# SaLAltimeter.net
KiCad netlist of a schematic drawn in EAGLE
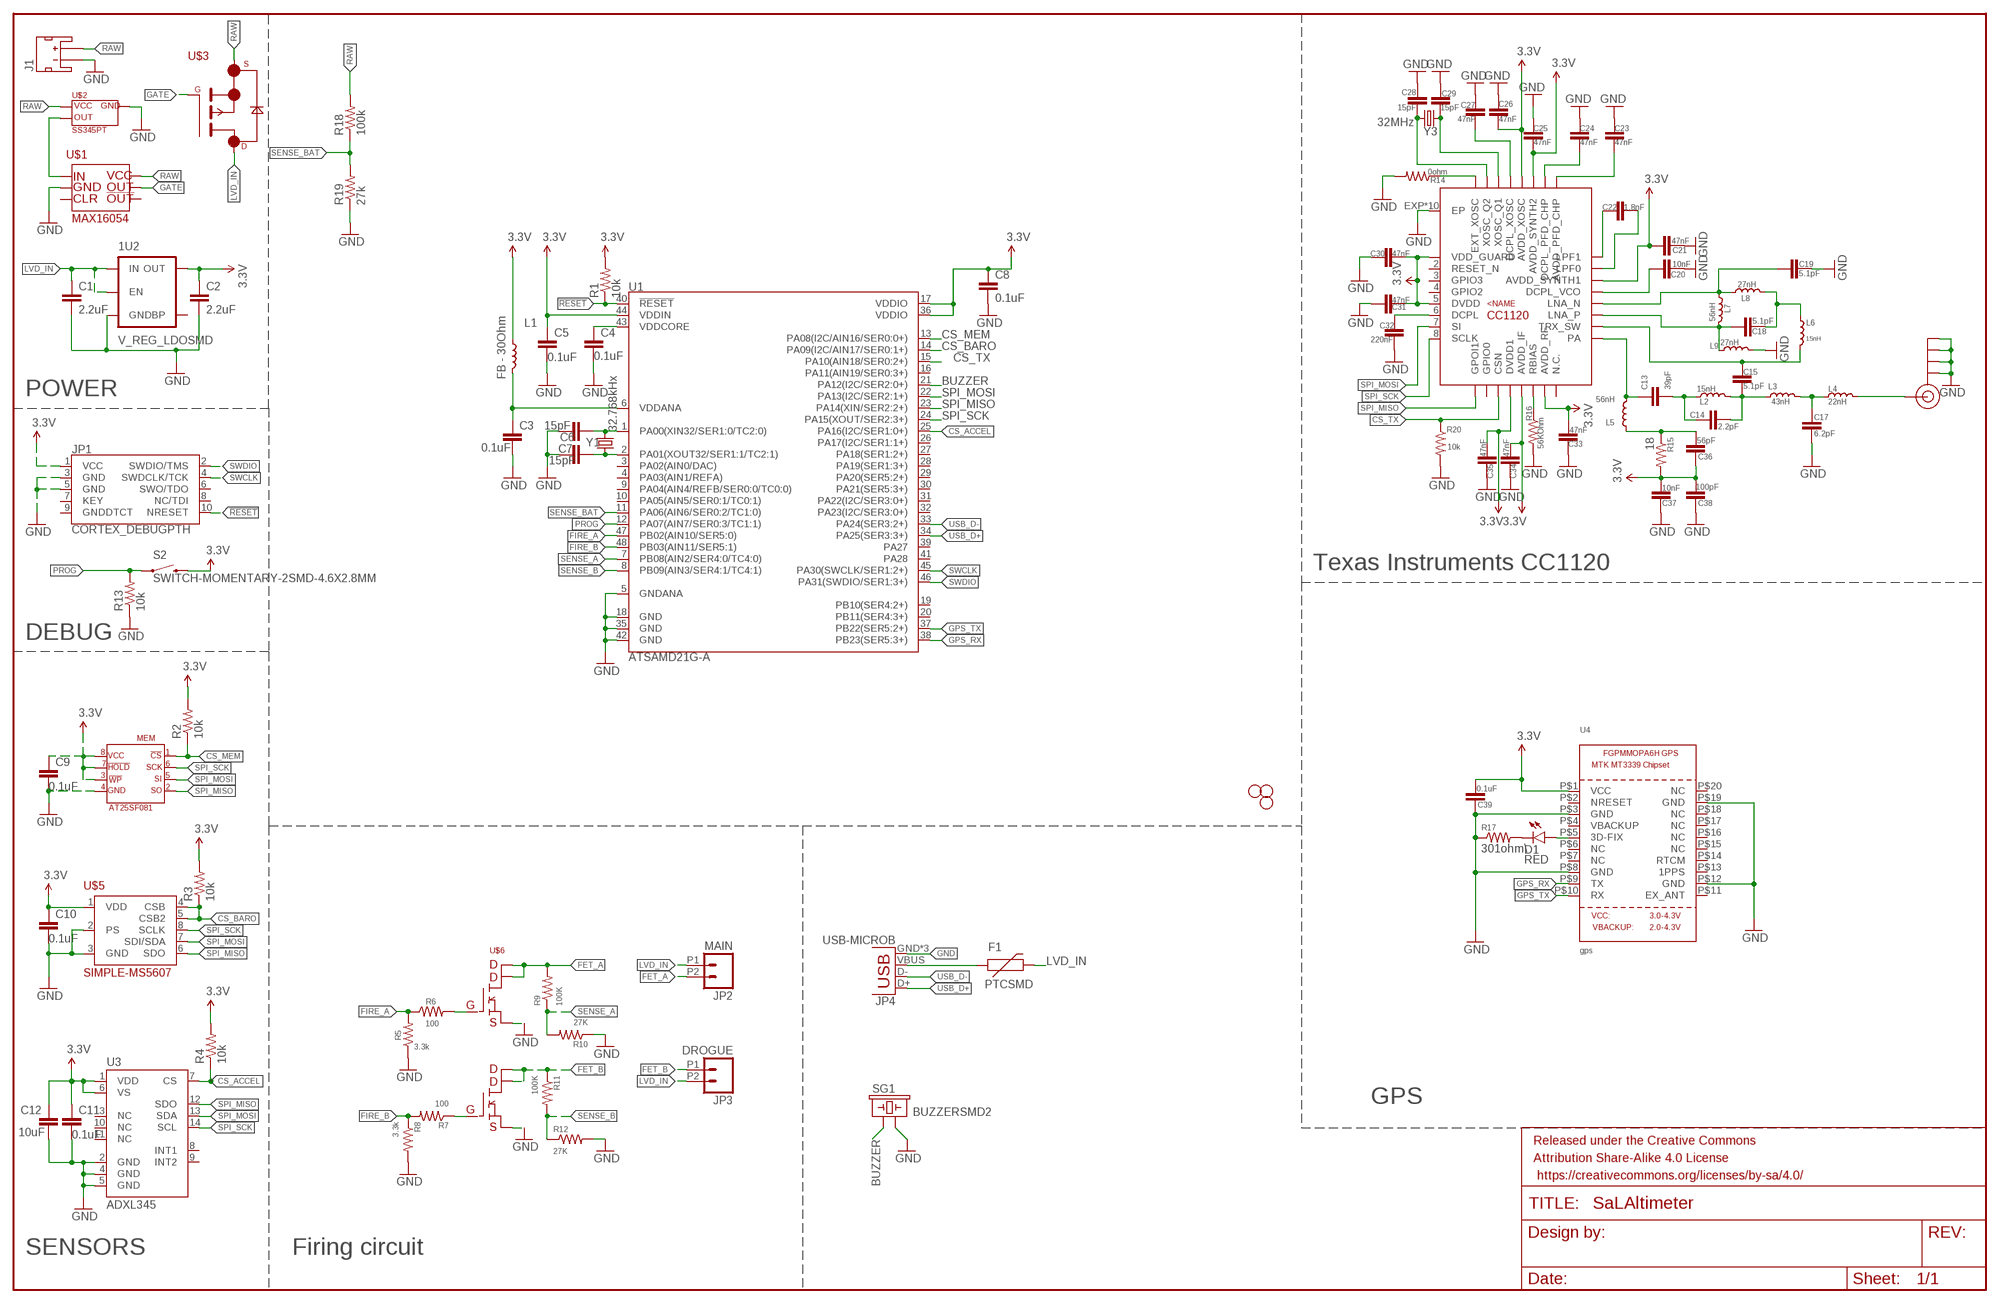
[diagram p0: schematic, sheet 1]

(export (version "E")
  (design (tool "Eeschema 10.0.6"))
  (components
    (comp (ref "1U2")
      (value "V_REG_LDOSMD")
      (footprint "eagle-import:SOT23-5")
      (libsource (lib "eagle-import") (part "V_REG_LDOSMD"))
    )
    (comp (ref "C1")
      (value "2.2uF")
      (footprint "eagle-import:0603-CAP")
      (libsource (lib "eagle-import") (part "CAP0603-CAP"))
    )
    (comp (ref "C2")
      (value "2.2uF")
      (footprint "eagle-import:0603-CAP")
      (libsource (lib "eagle-import") (part "CAP0603-CAP"))
    )
    (comp (ref "C3")
      (value "0.1uF")
      (footprint "eagle-import:0402-CAP")
      (libsource (lib "eagle-import") (part "SparkFun-Passives_CAP0402-CAP"))
    )
    (comp (ref "C4")
      (value "0.1uF")
      (footprint "eagle-import:0402-CAP")
      (libsource (lib "eagle-import") (part "SparkFun-Passives_CAP0402-CAP"))
    )
    (comp (ref "C5")
      (value "0.1uF")
      (footprint "eagle-import:0402-CAP")
      (libsource (lib "eagle-import") (part "SparkFun-Passives_CAP0402-CAP"))
    )
    (comp (ref "C6")
      (value "15pF")
      (footprint "eagle-import:0402-CAP")
      (libsource (lib "eagle-import") (part "SparkFun-Passives_CAP0402-CAP"))
    )
    (comp (ref "C7")
      (value "15pF")
      (footprint "eagle-import:0402-CAP")
      (libsource (lib "eagle-import") (part "SparkFun-Passives_CAP0402-CAP"))
    )
    (comp (ref "C8")
      (value "0.1uF")
      (footprint "eagle-import:0402-CAP")
      (libsource (lib "eagle-import") (part "SparkFun-Passives_CAP0402-CAP"))
    )
    (comp (ref "C9")
      (value "0.1uF")
      (footprint "eagle-import:0402-CAP")
      (libsource (lib "eagle-import") (part "SparkFun-Passives_CAP0402-CAP"))
    )
    (comp (ref "C10")
      (value "0.1uF")
      (footprint "eagle-import:0402-CAP")
      (libsource (lib "eagle-import") (part "SparkFun-Passives_CAP0402-CAP"))
    )
    (comp (ref "C11")
      (value "0.1uF")
      (footprint "eagle-import:0402-CAP")
      (libsource (lib "eagle-import") (part "SparkFun-Passives_CAP0402-CAP"))
    )
    (comp (ref "C12")
      (value "10uF")
      (footprint "eagle-import:0402-CAP")
      (libsource (lib "eagle-import") (part "SparkFun-Passives_CAP0402-CAP"))
    )
    (comp (ref "C13")
      (value "39pF")
      (footprint "eagle-import:0402-CAP")
      (libsource (lib "eagle-import") (part "CAP0402-CAP"))
    )
    (comp (ref "C14")
      (value "2.2pF")
      (footprint "eagle-import:0402-CAP")
      (libsource (lib "eagle-import") (part "CAP0402-CAP"))
    )
    (comp (ref "C15")
      (value "5.1pF")
      (footprint "eagle-import:0402-CAP")
      (libsource (lib "eagle-import") (part "CAP0402-CAP"))
    )
    (comp (ref "C17")
      (value "6.2pF")
      (footprint "eagle-import:0402-CAP")
      (libsource (lib "eagle-import") (part "CAP0402-CAP"))
    )
    (comp (ref "C18")
      (value "5.1pF")
      (footprint "eagle-import:0402-CAP")
      (libsource (lib "eagle-import") (part "CAP0402-CAP"))
    )
    (comp (ref "C19")
      (value "5.1pF")
      (footprint "eagle-import:0402-CAP")
      (libsource (lib "eagle-import") (part "CAP0402-CAP"))
    )
    (comp (ref "C20")
      (value "10nF")
      (footprint "eagle-import:0402-CAP")
      (libsource (lib "eagle-import") (part "CAP0402-CAP"))
    )
    (comp (ref "C21")
      (value "47nF")
      (footprint "eagle-import:0402-CAP")
      (libsource (lib "eagle-import") (part "CAP0402-CAP"))
    )
    (comp (ref "C22")
      (value "1.8nF")
      (footprint "eagle-import:0402-CAP")
      (libsource (lib "eagle-import") (part "CAP0402-CAP"))
    )
    (comp (ref "C23")
      (value "47nF")
      (footprint "eagle-import:0402-CAP")
      (libsource (lib "eagle-import") (part "CAP0402-CAP"))
    )
    (comp (ref "C24")
      (value "47nF")
      (footprint "eagle-import:0402-CAP")
      (libsource (lib "eagle-import") (part "CAP0402-CAP"))
    )
    (comp (ref "C25")
      (value "47nF")
      (footprint "eagle-import:0402-CAP")
      (libsource (lib "eagle-import") (part "CAP0402-CAP"))
    )
    (comp (ref "C26")
      (value "47nF")
      (footprint "eagle-import:0402-CAP")
      (libsource (lib "eagle-import") (part "CAP0402-CAP"))
    )
    (comp (ref "C27")
      (value "47nF")
      (footprint "eagle-import:0402-CAP")
      (libsource (lib "eagle-import") (part "CAP0402-CAP"))
    )
    (comp (ref "C28")
      (value "15pF")
      (footprint "eagle-import:0402-CAP")
      (libsource (lib "eagle-import") (part "CAP0402-CAP"))
    )
    (comp (ref "C29")
      (value "15pF")
      (footprint "eagle-import:0402-CAP")
      (libsource (lib "eagle-import") (part "CAP0402-CAP"))
    )
    (comp (ref "C30")
      (value "47nF")
      (footprint "eagle-import:0402-CAP")
      (libsource (lib "eagle-import") (part "CAP0402-CAP"))
    )
    (comp (ref "C31")
      (value "47nF")
      (footprint "eagle-import:0402-CAP")
      (libsource (lib "eagle-import") (part "CAP0402-CAP"))
    )
    (comp (ref "C32")
      (value "220nF")
      (footprint "eagle-import:0402-CAP")
      (libsource (lib "eagle-import") (part "CAP0402-CAP"))
    )
    (comp (ref "C33")
      (value "47nF")
      (footprint "eagle-import:0402-CAP")
      (libsource (lib "eagle-import") (part "CAP0402-CAP"))
    )
    (comp (ref "C34")
      (value "47nF")
      (footprint "eagle-import:0402-CAP")
      (libsource (lib "eagle-import") (part "CAP0402-CAP"))
    )
    (comp (ref "C35")
      (value "47nF")
      (footprint "eagle-import:0402-CAP")
      (libsource (lib "eagle-import") (part "CAP0402-CAP"))
    )
    (comp (ref "C36")
      (value "56pF")
      (footprint "eagle-import:0402-CAP")
      (libsource (lib "eagle-import") (part "CAP0402-CAP"))
    )
    (comp (ref "C37")
      (value "10nF")
      (footprint "eagle-import:0402-CAP")
      (libsource (lib "eagle-import") (part "CAP0402-CAP"))
    )
    (comp (ref "C38")
      (value "100pF")
      (footprint "eagle-import:0402-CAP")
      (libsource (lib "eagle-import") (part "CAP0402-CAP"))
    )
    (comp (ref "C39")
      (value "0.1uF")
      (footprint "eagle-import:0402-CAP")
      (libsource (lib "eagle-import") (part "CAP0402-CAP"))
    )
    (comp (ref "D1")
      (value "RED")
      (footprint "eagle-import:LED-0603")
      (libsource (lib "eagle-import") (part "LED-RED0603"))
    )
    (comp (ref "F1")
      (value "PTCSMD")
      (footprint "eagle-import:PTC-1206")
      (libsource (lib "eagle-import") (part "PTCSMD"))
    )
    (comp (ref "FRAME1")
      (value "FRAME-LEDGER")
      (footprint "eagle-import:CREATIVE_COMMONS")
      (libsource (lib "eagle-import") (part "FRAME-LEDGER"))
    )
    (comp (ref "J$1")
      (value "SMA_EDGE")
      (footprint "eagle-import:SMA-EDGE")
      (libsource (lib "eagle-import") (part "SMA_EDGE"))
    )
    (comp (ref "J1")
      (value "BAT")
      (footprint "eagle-import:JST-2-SMD")
      (libsource (lib "eagle-import") (part "JST_2MM_MALE"))
    )
    (comp (ref "JP1")
      (value "CORTEX_DEBUGPTH")
      (footprint "eagle-import:2X5-PTH-1.27MM")
      (libsource (lib "eagle-import") (part "CORTEX_DEBUGPTH"))
    )
    (comp (ref "JP2")
      (value "MAIN")
      (footprint "eagle-import:1X02_2.54_SCREWTERM")
      (libsource (lib "eagle-import") (part "M022.54MM_SCREWTERM"))
    )
    (comp (ref "JP3")
      (value "DROGUE")
      (footprint "eagle-import:1X02_2.54_SCREWTERM")
      (libsource (lib "eagle-import") (part "M022.54MM_SCREWTERM"))
    )
    (comp (ref "JP4")
      (value "USB-MICROB")
      (footprint "eagle-import:USB-MICROB")
      (libsource (lib "eagle-import") (part "USB-MICROB"))
    )
    (comp (ref "L1")
      (value "FB - 30Ohm")
      (footprint "eagle-import:0603")
      (libsource (lib "eagle-import") (part "INDUCTOR0603"))
    )
    (comp (ref "L2")
      (value "15nH")
      (footprint "eagle-import:C0402")
      (libsource (lib "eagle-import") (part "INDUCTOR0402"))
    )
    (comp (ref "L3")
      (value "43nH")
      (footprint "eagle-import:C0402")
      (libsource (lib "eagle-import") (part "INDUCTOR0402"))
    )
    (comp (ref "L4")
      (value "22nH")
      (footprint "eagle-import:C0402")
      (libsource (lib "eagle-import") (part "INDUCTOR0402"))
    )
    (comp (ref "L5")
      (value "56nH")
      (footprint "eagle-import:C0402")
      (libsource (lib "eagle-import") (part "INDUCTOR0402"))
    )
    (comp (ref "L6")
      (value "15nH")
      (footprint "eagle-import:C0402")
      (libsource (lib "eagle-import") (part "INDUCTOR0402"))
    )
    (comp (ref "L7")
      (value "56nH")
      (footprint "eagle-import:C0402")
      (libsource (lib "eagle-import") (part "INDUCTOR0402"))
    )
    (comp (ref "L8")
      (value "27nH")
      (footprint "eagle-import:C0402")
      (libsource (lib "eagle-import") (part "INDUCTOR0402"))
    )
    (comp (ref "L9")
      (value "27nH")
      (footprint "eagle-import:C0402")
      (libsource (lib "eagle-import") (part "INDUCTOR0402"))
    )
    (comp (ref "MEM")
      (value "AT25SF081")
      (footprint "eagle-import:AT25SF081")
      (libsource (lib "eagle-import") (part "AT25SF081"))
    )
    (comp (ref "R1")
      (value "10k")
      (footprint "eagle-import:0402-RES")
      (libsource (lib "eagle-import") (part "RESISTOR0402-RES"))
    )
    (comp (ref "R2")
      (value "10k")
      (footprint "eagle-import:0402-RES")
      (libsource (lib "eagle-import") (part "RESISTOR0402-RES"))
    )
    (comp (ref "R3")
      (value "10k")
      (footprint "eagle-import:0402-RES")
      (libsource (lib "eagle-import") (part "RESISTOR0402-RES"))
    )
    (comp (ref "R4")
      (value "10k")
      (footprint "eagle-import:0402-RES")
      (libsource (lib "eagle-import") (part "RESISTOR0402-RES"))
    )
    (comp (ref "R5")
      (value "3.3k")
      (footprint "eagle-import:0402-RES")
      (libsource (lib "eagle-import") (part "RESISTOR0402"))
    )
    (comp (ref "R6")
      (value "100")
      (footprint "eagle-import:0402-RES")
      (libsource (lib "eagle-import") (part "RESISTOR0402"))
    )
    (comp (ref "R7")
      (value "100")
      (footprint "eagle-import:0402-RES")
      (libsource (lib "eagle-import") (part "RESISTOR0402"))
    )
    (comp (ref "R8")
      (value "3.3k")
      (footprint "eagle-import:0402-RES")
      (libsource (lib "eagle-import") (part "RESISTOR0402"))
    )
    (comp (ref "R9")
      (value "100K")
      (footprint "eagle-import:0402-RES")
      (libsource (lib "eagle-import") (part "RESISTOR0402"))
    )
    (comp (ref "R10")
      (value "27K")
      (footprint "eagle-import:0402-RES")
      (libsource (lib "eagle-import") (part "RESISTOR0402"))
    )
    (comp (ref "R11")
      (value "100K")
      (footprint "eagle-import:0402-RES")
      (libsource (lib "eagle-import") (part "RESISTOR0402"))
    )
    (comp (ref "R12")
      (value "27K")
      (footprint "eagle-import:0402-RES")
      (libsource (lib "eagle-import") (part "RESISTOR0402"))
    )
    (comp (ref "R13")
      (value "10k")
      (footprint "eagle-import:0402-RES")
      (libsource (lib "eagle-import") (part "RESISTOR0402-RES"))
    )
    (comp (ref "R14")
      (value "0ohm")
      (footprint "eagle-import:0402-RES")
      (libsource (lib "eagle-import") (part "RESISTOR0402-RES"))
    )
    (comp (ref "R15")
      (value "18")
      (footprint "eagle-import:0402-RES")
      (libsource (lib "eagle-import") (part "RESISTOR0402-RES"))
    )
    (comp (ref "R16")
      (value "56KOhm")
      (footprint "eagle-import:0402-RES")
      (libsource (lib "eagle-import") (part "RESISTOR0402-RES"))
    )
    (comp (ref "R17")
      (value "301ohm\\")
      (footprint "eagle-import:0402-RES")
      (libsource (lib "eagle-import") (part "RESISTOR0402-RES"))
    )
    (comp (ref "R18")
      (value "100k")
      (footprint "eagle-import:0402-RES")
      (libsource (lib "eagle-import") (part "RESISTOR0402-RES"))
    )
    (comp (ref "R19")
      (value "27k")
      (footprint "eagle-import:0402-RES")
      (libsource (lib "eagle-import") (part "RESISTOR0402-RES"))
    )
    (comp (ref "R20")
      (value "10k")
      (footprint "eagle-import:0402-RES")
      (libsource (lib "eagle-import") (part "RESISTOR0402-RES"))
    )
    (comp (ref "S2")
      (value "SWITCH-MOMENTARY-2SMD-4.6X2.8MM")
      (footprint "eagle-import:TACTILE_SWITCH_SMD_4.6X2.8MM")
      (libsource (lib "eagle-import") (part "SWITCH-MOMENTARY-2SMD-4.6X2.8MM"))
    )
    (comp (ref "SG1")
      (value "BUZZERSMD2")
      (footprint "eagle-import:BUZZER-CCV")
      (libsource (lib "eagle-import") (part "BUZZERSMD2"))
    )
    (comp (ref "STANDOFF1")
      (value "STAND-OFF")
      (footprint "eagle-import:STAND-OFF")
      (libsource (lib "eagle-import") (part "STAND-OFF"))
    )
    (comp (ref "STANDOFF2")
      (value "STAND-OFF")
      (footprint "eagle-import:STAND-OFF")
      (libsource (lib "eagle-import") (part "STAND-OFF"))
    )
    (comp (ref "STANDOFF3")
      (value "STAND-OFF")
      (footprint "eagle-import:STAND-OFF")
      (libsource (lib "eagle-import") (part "STAND-OFF"))
    )
    (comp (ref "U$1")
      (value "MAX16054")
      (footprint "eagle-import:MAX16054")
      (libsource (lib "eagle-import") (part "MAX16054"))
    )
    (comp (ref "U$2")
      (value "SS345PT")
      (footprint "eagle-import:SS345PT")
      (libsource (lib "eagle-import") (part "SS345PT"))
    )
    (comp (ref "U$3")
      (value "SI7615ADN")
      (footprint "eagle-import:SI7615ADN")
      (libsource (lib "eagle-import") (part "SI7615ADN"))
    )
    (comp (ref "U$5")
      (value "SIMPLE-MS5607")
      (footprint "eagle-import:MS5607")
      (libsource (lib "eagle-import") (part "SIMPLE-MS5607"))
    )
    (comp (ref "U$6")
      (value "SI7232DN")
      (footprint "eagle-import:SI7232DN")
      (libsource (lib "eagle-import") (part "SI7232DN"))
    )
    (comp (ref "U1")
      (value "ATSAMD21G-A")
      (footprint "eagle-import:TQFP-48")
      (libsource (lib "eagle-import") (part "ATSAMD21G-A"))
    )
    (comp (ref "U2")
      (value "CC1120")
      (footprint "eagle-import:CC1120")
      (libsource (lib "eagle-import") (part "CC1120"))
    )
    (comp (ref "U3")
      (value "ADXL345")
      (footprint "eagle-import:LGA14")
      (libsource (lib "eagle-import") (part "ADXL345"))
    )
    (comp (ref "U4")
      (value "gps")
      (footprint "eagle-import:FGPMMOPA6H")
      (libsource (lib "eagle-import") (part "GPS_FGPMMOPA6H"))
    )
    (comp (ref "Y1")
      (value "32.768kHx")
      (footprint "eagle-import:CRYSTAL-SMD-3.2X1.5MM")
      (libsource (lib "eagle-import") (part "CRYSTAL3.2X1.5MM"))
    )
    (comp (ref "Y3")
      (value "32MHz")
      (footprint "eagle-import:CRYSTAL-SMD-5X3")
      (libsource (lib "eagle-import") (part "CRYSTAL5X3"))
    )
  )
  (nets
    (net (code "1") (name "/BUZZER") (class "Default")
      (node (ref "SG1") (pin "+") (pinfunction "1_+") (pintype "passive"))
      (node (ref "U1") (pin "21") (pinfunction "PA12(I2C/SER2:0+)_21") (pintype "bidirectional"))
    )
    (net (code "2") (name "/~{RESET}") (class "Default")
      (node (ref "JP1") (pin "10") (pinfunction "NRESET_10") (pintype "bidirectional"))
      (node (ref "R1") (pin "1") (pinfunction "1_1") (pintype "passive"))
      (node (ref "U1") (pin "40") (pinfunction "~{RESET}_40") (pintype "bidirectional"))
    )
    (net (code "3") (name "3.3V") (class "Default")
      (node (ref "1U2") (pin "5") (pinfunction "OUT_5") (pintype "passive"))
      (node (ref "C10") (pin "1") (pinfunction "1_1") (pintype "passive"))
      (node (ref "C11") (pin "1") (pinfunction "1_1") (pintype "passive"))
      (node (ref "C12") (pin "1") (pinfunction "1_1") (pintype "passive"))
      (node (ref "C2") (pin "1") (pinfunction "1_1") (pintype "passive"))
      (node (ref "C21") (pin "1") (pinfunction "1_1") (pintype "passive"))
      (node (ref "C25") (pin "2") (pinfunction "2_2") (pintype "passive"))
      (node (ref "C26") (pin "2") (pinfunction "2_2") (pintype "passive"))
      (node (ref "C30") (pin "2") (pinfunction "2_2") (pintype "passive"))
      (node (ref "C31") (pin "2") (pinfunction "2_2") (pintype "passive"))
      (node (ref "C33") (pin "2") (pinfunction "2_2") (pintype "passive"))
      (node (ref "C34") (pin "2") (pinfunction "2_2") (pintype "passive"))
      (node (ref "C35") (pin "2") (pinfunction "2_2") (pintype "passive"))
      (node (ref "C36") (pin "1") (pinfunction "1_1") (pintype "passive"))
      (node (ref "C37") (pin "2") (pinfunction "2_2") (pintype "passive"))
      (node (ref "C38") (pin "2") (pinfunction "2_2") (pintype "passive"))
      (node (ref "C39") (pin "2") (pinfunction "2_2") (pintype "passive"))
      (node (ref "C5") (pin "1") (pinfunction "1_1") (pintype "passive"))
      (node (ref "C8") (pin "1") (pinfunction "1_1") (pintype "passive"))
      (node (ref "C9") (pin "1") (pinfunction "1_1") (pintype "passive"))
      (node (ref "JP1") (pin "1") (pinfunction "VCC_1") (pintype "bidirectional"))
      (node (ref "L1") (pin "1") (pinfunction "1_1") (pintype "passive"))
      (node (ref "MEM") (pin "!HOLD") (pinfunction "~{HOLD}_!HOLD") (pintype "bidirectional"))
      (node (ref "MEM") (pin "!WP") (pinfunction "~{WP}_!WP") (pintype "bidirectional"))
      (node (ref "MEM") (pin "VCC") (pinfunction "VCC_VCC") (pintype "bidirectional"))
      (node (ref "R1") (pin "2") (pinfunction "2_2") (pintype "passive"))
      (node (ref "R15") (pin "2") (pinfunction "2_2") (pintype "passive"))
      (node (ref "R2") (pin "2") (pinfunction "2_2") (pintype "passive"))
      (node (ref "R3") (pin "2") (pinfunction "2_2") (pintype "passive"))
      (node (ref "R4") (pin "2") (pinfunction "2_2") (pintype "passive"))
      (node (ref "S2") (pin "3") (pinfunction "2_3") (pintype "passive"))
      (node (ref "S2") (pin "4") (pinfunction "2_4") (pintype "passive"))
      (node (ref "U$5") (pin "1") (pinfunction "VDD_1") (pintype "bidirectional"))
      (node (ref "U1") (pin "17") (pinfunction "VDDIO_17") (pintype "bidirectional"))
      (node (ref "U1") (pin "36") (pinfunction "VDDIO_36") (pintype "bidirectional"))
      (node (ref "U1") (pin "44") (pinfunction "VDDIN_44") (pintype "bidirectional"))
      (node (ref "U2") (pin "1") (pinfunction "VDD_GUARD_1") (pintype "bidirectional"))
      (node (ref "U2") (pin "12") (pinfunction "DVDD1_12") (pintype "bidirectional"))
      (node (ref "U2") (pin "13") (pinfunction "AVDD_IF_13") (pintype "bidirectional"))
      (node (ref "U2") (pin "15") (pinfunction "AVDD_RF_15") (pintype "bidirectional"))
      (node (ref "U2") (pin "22") (pinfunction "AVDD_SYNTH1_22") (pintype "bidirectional"))
      (node (ref "U2") (pin "27") (pinfunction "AVDD_SYNTH2_27") (pintype "bidirectional"))
      (node (ref "U2") (pin "28") (pinfunction "AVDD_XOSC_28") (pintype "bidirectional"))
      (node (ref "U2") (pin "5") (pinfunction "DVDD_5") (pintype "bidirectional"))
      (node (ref "U3") (pin "1") (pinfunction "VDD_1") (pintype "bidirectional"))
      (node (ref "U3") (pin "6") (pinfunction "VS_6") (pintype "bidirectional"))
      (node (ref "U4") (pin "P$1") (pinfunction "VCC_P$1") (pintype "bidirectional"))
    )
    (net (code "4") (name "CS_ACCEL") (class "Default")
      (node (ref "R4") (pin "1") (pinfunction "1_1") (pintype "passive"))
      (node (ref "U1") (pin "25") (pinfunction "PA16(I2C/SER1:0+)_25") (pintype "bidirectional"))
      (node (ref "U3") (pin "7") (pinfunction "CS_7") (pintype "bidirectional"))
    )
    (net (code "5") (name "CS_BARO") (class "Default")
      (node (ref "R3") (pin "1") (pinfunction "1_1") (pintype "passive"))
      (node (ref "U$5") (pin "4") (pinfunction "CSB_4") (pintype "bidirectional"))
      (node (ref "U$5") (pin "5") (pinfunction "CSB2_5") (pintype "bidirectional"))
      (node (ref "U1") (pin "14") (pinfunction "PA09(I2C/AIN17/SER0:1+)_14") (pintype "bidirectional"))
    )
    (net (code "6") (name "CS_MEM") (class "Default")
      (node (ref "MEM") (pin "!CS") (pinfunction "~{CS}_!CS") (pintype "bidirectional"))
      (node (ref "R2") (pin "1") (pinfunction "1_1") (pintype "passive"))
      (node (ref "U1") (pin "13") (pinfunction "PA08(I2C/AIN16/SER0:0+)_13") (pintype "bidirectional"))
    )
    (net (code "7") (name "CS_TX") (class "Default")
      (node (ref "R20") (pin "1") (pinfunction "1_1") (pintype "passive"))
      (node (ref "U1") (pin "15") (pinfunction "PA10(AIN18/SER0:2+)_15") (pintype "bidirectional"))
      (node (ref "U2") (pin "11") (pinfunction "CSN_11") (pintype "bidirectional"))
    )
    (net (code "8") (name "FET_A") (class "Default")
      (node (ref "JP2") (pin "P2") (pinfunction "2_P2") (pintype "passive"))
      (node (ref "R9") (pin "2") (pinfunction "2_2") (pintype "passive"))
      (node (ref "U$6") (pin "7") (pinfunction "PIN7_7") (pintype "bidirectional"))
      (node (ref "U$6") (pin "8") (pinfunction "PIN8_8") (pintype "bidirectional"))
    )
    (net (code "9") (name "FET_B") (class "Default")
      (node (ref "JP3") (pin "P1") (pinfunction "1_P1") (pintype "passive"))
      (node (ref "R11") (pin "1") (pinfunction "1_1") (pintype "passive"))
      (node (ref "U$6") (pin "5") (pinfunction "PIN5_5") (pintype "bidirectional"))
      (node (ref "U$6") (pin "6") (pinfunction "PIN6_6") (pintype "bidirectional"))
    )
    (net (code "10") (name "FIRE_A") (class "Default")
      (node (ref "R5") (pin "2") (pinfunction "2_2") (pintype "passive"))
      (node (ref "R6") (pin "1") (pinfunction "1_1") (pintype "passive"))
      (node (ref "U1") (pin "47") (pinfunction "PB02(AIN10/SER5:0)_47") (pintype "bidirectional"))
    )
    (net (code "11") (name "FIRE_B") (class "Default")
      (node (ref "R7") (pin "2") (pinfunction "2_2") (pintype "passive"))
      (node (ref "R8") (pin "1") (pinfunction "1_1") (pintype "passive"))
      (node (ref "U1") (pin "48") (pinfunction "PB03(AIN11/SER5:1)_48") (pintype "bidirectional"))
    )
    (net (code "12") (name "GATE") (class "Default")
      (node (ref "U$1") (pin "OUT") (pinfunction "OUT_OUT") (pintype "bidirectional"))
      (node (ref "U$3") (pin "G") (pinfunction "G_G") (pintype "bidirectional"))
    )
    (net (code "13") (name "GND") (class "Default")
      (node (ref "1U2") (pin "2") (pinfunction "GND_2") (pintype "input"))
      (node (ref "C1") (pin "2") (pinfunction "2_2") (pintype "passive"))
      (node (ref "C10") (pin "2") (pinfunction "2_2") (pintype "passive"))
      (node (ref "C11") (pin "2") (pinfunction "2_2") (pintype "passive"))
      (node (ref "C12") (pin "2") (pinfunction "2_2") (pintype "passive"))
      (node (ref "C17") (pin "2") (pinfunction "2_2") (pintype "passive"))
      (node (ref "C19") (pin "2") (pinfunction "2_2") (pintype "passive"))
      (node (ref "C2") (pin "2") (pinfunction "2_2") (pintype "passive"))
      (node (ref "C20") (pin "2") (pinfunction "2_2") (pintype "passive"))
      (node (ref "C21") (pin "2") (pinfunction "2_2") (pintype "passive"))
      (node (ref "C23") (pin "1") (pinfunction "1_1") (pintype "passive"))
      (node (ref "C24") (pin "1") (pinfunction "1_1") (pintype "passive"))
      (node (ref "C25") (pin "1") (pinfunction "1_1") (pintype "passive"))
      (node (ref "C26") (pin "1") (pinfunction "1_1") (pintype "passive"))
      (node (ref "C27") (pin "1") (pinfunction "1_1") (pintype "passive"))
      (node (ref "C28") (pin "1") (pinfunction "1_1") (pintype "passive"))
      (node (ref "C29") (pin "1") (pinfunction "1_1") (pintype "passive"))
      (node (ref "C3") (pin "2") (pinfunction "2_2") (pintype "passive"))
      (node (ref "C30") (pin "1") (pinfunction "1_1") (pintype "passive"))
      (node (ref "C31") (pin "1") (pinfunction "1_1") (pintype "passive"))
      (node (ref "C32") (pin "1") (pinfunction "1_1") (pintype "passive"))
      (node (ref "C33") (pin "1") (pinfunction "1_1") (pintype "passive"))
      (node (ref "C34") (pin "1") (pinfunction "1_1") (pintype "passive"))
      (node (ref "C35") (pin "1") (pinfunction "1_1") (pintype "passive"))
      (node (ref "C37") (pin "1") (pinfunction "1_1") (pintype "passive"))
      (node (ref "C38") (pin "1") (pinfunction "1_1") (pintype "passive"))
      (node (ref "C39") (pin "1") (pinfunction "1_1") (pintype "passive"))
      (node (ref "C4") (pin "2") (pinfunction "2_2") (pintype "passive"))
      (node (ref "C5") (pin "2") (pinfunction "2_2") (pintype "passive"))
      (node (ref "C6") (pin "2") (pinfunction "2_2") (pintype "passive"))
      (node (ref "C7") (pin "2") (pinfunction "2_2") (pintype "passive"))
      (node (ref "C8") (pin "2") (pinfunction "2_2") (pintype "passive"))
      (node (ref "C9") (pin "2") (pinfunction "2_2") (pintype "passive"))
      (node (ref "J$1") (pin "GND@0") (pinfunction "GND_GND@0") (pintype "bidirectional"))
      (node (ref "J$1") (pin "GND@1") (pinfunction "GND_GND@1") (pintype "bidirectional"))
      (node (ref "J$1") (pin "GND@2") (pinfunction "GND_GND@2") (pintype "bidirectional"))
      (node (ref "J$1") (pin "GND@3") (pinfunction "GND_GND@3") (pintype "bidirectional"))
      (node (ref "J1") (pin "1") (pinfunction "-_1") (pintype "bidirectional"))
      (node (ref "JP1") (pin "3") (pinfunction "GND_3") (pintype "bidirectional"))
      (node (ref "JP1") (pin "5") (pinfunction "GND_5") (pintype "bidirectional"))
      (node (ref "JP4") (pin "GND") (pinfunction "GND_GND") (pintype "bidirectional"))
      (node (ref "JP4") (pin "MT1") (pinfunction "GND_MT1") (pintype "bidirectional"))
      (node (ref "JP4") (pin "MT2") (pinfunction "GND_MT2") (pintype "bidirectional"))
      (node (ref "L9") (pin "2") (pinfunction "2_2") (pintype "passive"))
      (node (ref "MEM") (pin "GND") (pinfunction "GND_GND") (pintype "bidirectional"))
      (node (ref "R10") (pin "1") (pinfunction "1_1") (pintype "passive"))
      (node (ref "R12") (pin "2") (pinfunction "2_2") (pintype "passive"))
      (node (ref "R13") (pin "1") (pinfunction "1_1") (pintype "passive"))
      (node (ref "R14") (pin "2") (pinfunction "2_2") (pintype "passive"))
      (node (ref "R16") (pin "2") (pinfunction "2_2") (pintype "passive"))
      (node (ref "R17") (pin "1") (pinfunction "1_1") (pintype "passive"))
      (node (ref "R19") (pin "1") (pinfunction "1_1") (pintype "passive"))
      (node (ref "R20") (pin "2") (pinfunction "2_2") (pintype "passive"))
      (node (ref "R5") (pin "1") (pinfunction "1_1") (pintype "passive"))
      (node (ref "R8") (pin "2") (pinfunction "2_2") (pintype "passive"))
      (node (ref "SG1") (pin "-") (pinfunction "2_-") (pintype "passive"))
      (node (ref "U$1") (pin "GND") (pinfunction "GND_GND") (pintype "bidirectional"))
      (node (ref "U$2") (pin "GND") (pinfunction "GND_GND") (pintype "bidirectional"))
      (node (ref "U$5") (pin "2") (pinfunction "PS_2") (pintype "bidirectional"))
      (node (ref "U$5") (pin "3") (pinfunction "GND_3") (pintype "bidirectional"))
      (node (ref "U$6") (pin "1") (pinfunction "PIN1_1") (pintype "bidirectional"))
      (node (ref "U$6") (pin "3") (pinfunction "PIN3_3") (pintype "bidirectional"))
      (node (ref "U1") (pin "18") (pinfunction "GND_18") (pintype "bidirectional"))
      (node (ref "U1") (pin "35") (pinfunction "GND_35") (pintype "bidirectional"))
      (node (ref "U1") (pin "42") (pinfunction "GND_42") (pintype "bidirectional"))
      (node (ref "U1") (pin "5") (pinfunction "GNDANA_5") (pintype "bidirectional"))
      (node (ref "U2") (pin "EXP") (pinfunction "EP_EXP") (pintype "bidirectional"))
      (node (ref "U2") (pin "EXP@1") (pinfunction "EP_EXP@1") (pintype "bidirectional"))
      (node (ref "U2") (pin "EXP@2") (pinfunction "EP_EXP@2") (pintype "bidirectional"))
      (node (ref "U2") (pin "EXP@3") (pinfunction "EP_EXP@3") (pintype "bidirectional"))
      (node (ref "U2") (pin "EXP@4") (pinfunction "EP_EXP@4") (pintype "bidirectional"))
      (node (ref "U2") (pin "EXP@5") (pinfunction "EP_EXP@5") (pintype "bidirectional"))
      (node (ref "U2") (pin "EXP@6") (pinfunction "EP_EXP@6") (pintype "bidirectional"))
      (node (ref "U2") (pin "EXP@7") (pinfunction "EP_EXP@7") (pintype "bidirectional"))
      (node (ref "U2") (pin "EXP@8") (pinfunction "EP_EXP@8") (pintype "bidirectional"))
      (node (ref "U2") (pin "EXP@9") (pinfunction "EP_EXP@9") (pintype "bidirectional"))
      (node (ref "U3") (pin "2") (pinfunction "GND_2") (pintype "bidirectional"))
      (node (ref "U3") (pin "4") (pinfunction "GND_4") (pintype "bidirectional"))
      (node (ref "U3") (pin "5") (pinfunction "GND_5") (pintype "bidirectional"))
      (node (ref "U4") (pin "P$12") (pinfunction "GND_P$12") (pintype "bidirectional"))
      (node (ref "U4") (pin "P$19") (pinfunction "GND_P$19") (pintype "bidirectional"))
      (node (ref "U4") (pin "P$3") (pinfunction "GND_P$3") (pintype "bidirectional"))
      (node (ref "U4") (pin "P$8") (pinfunction "GND_P$8") (pintype "bidirectional"))
    )
    (net (code "14") (name "GPS_RX") (class "Default")
      (node (ref "U1") (pin "38") (pinfunction "PB23(SER5:3+)_38") (pintype "bidirectional"))
      (node (ref "U4") (pin "P$9") (pinfunction "TX_P$9") (pintype "bidirectional"))
    )
    (net (code "15") (name "GPS_TX") (class "Default")
      (node (ref "U1") (pin "37") (pinfunction "PB22(SER5:2+)_37") (pintype "bidirectional"))
      (node (ref "U4") (pin "P$10") (pinfunction "RX_P$10") (pintype "bidirectional"))
    )
    (net (code "16") (name "LVD_IN") (class "Default")
      (node (ref "1U2") (pin "1") (pinfunction "IN_1") (pintype "input"))
      (node (ref "1U2") (pin "3") (pinfunction "EN_3") (pintype "input"))
      (node (ref "C1") (pin "1") (pinfunction "1_1") (pintype "passive"))
      (node (ref "F1") (pin "2") (pinfunction "2_2") (pintype "bidirectional"))
      (node (ref "JP2") (pin "P1") (pinfunction "1_P1") (pintype "passive"))
      (node (ref "JP3") (pin "P2") (pinfunction "2_P2") (pintype "passive"))
      (node (ref "U$3") (pin "D1") (pinfunction "D_D1") (pintype "bidirectional"))
      (node (ref "U$3") (pin "D2") (pinfunction "D_D2") (pintype "bidirectional"))
      (node (ref "U$3") (pin "D3") (pinfunction "D_D3") (pintype "bidirectional"))
      (node (ref "U$3") (pin "D4") (pinfunction "D_D4") (pintype "bidirectional"))
    )
    (net (code "17") (name "Net-(C13-Pad2)") (class "Default")
      (node (ref "C13") (pin "2") (pinfunction "2_2") (pintype "passive"))
      (node (ref "C14") (pin "1") (pinfunction "1_1") (pintype "passive"))
      (node (ref "L2") (pin "1") (pinfunction "1_1") (pintype "passive"))
    )
    (net (code "18") (name "Net-(C14-Pad2)") (class "Default")
      (node (ref "C14") (pin "2") (pinfunction "2_2") (pintype "passive"))
      (node (ref "C15") (pin "1") (pinfunction "1_1") (pintype "passive"))
      (node (ref "L2") (pin "2") (pinfunction "2_2") (pintype "passive"))
      (node (ref "L3") (pin "1") (pinfunction "1_1") (pintype "passive"))
    )
    (net (code "19") (name "Net-(C17-Pad1)") (class "Default")
      (node (ref "C17") (pin "1") (pinfunction "1_1") (pintype "passive"))
      (node (ref "L3") (pin "2") (pinfunction "2_2") (pintype "passive"))
      (node (ref "L4") (pin "1") (pinfunction "1_1") (pintype "passive"))
    )
    (net (code "20") (name "Net-(C18-Pad2)") (class "Default")
      (node (ref "C18") (pin "2") (pinfunction "2_2") (pintype "passive"))
      (node (ref "L6") (pin "1") (pinfunction "1_1") (pintype "passive"))
      (node (ref "L8") (pin "2") (pinfunction "2_2") (pintype "passive"))
    )
    (net (code "21") (name "Net-(C36-Pad2)") (class "Default")
      (node (ref "C36") (pin "2") (pinfunction "2_2") (pintype "passive"))
      (node (ref "L5") (pin "1") (pinfunction "1_1") (pintype "passive"))
      (node (ref "R15") (pin "1") (pinfunction "1_1") (pintype "passive"))
    )
    (net (code "22") (name "Net-(D1-PadC)") (class "Default")
      (node (ref "D1") (pin "C") (pinfunction "C_C") (pintype "passive"))
      (node (ref "R17") (pin "2") (pinfunction "2_2") (pintype "passive"))
    )
    (net (code "23") (name "Net-(F1-Pad1)") (class "Default")
      (node (ref "F1") (pin "1") (pinfunction "1_1") (pintype "bidirectional"))
      (node (ref "JP4") (pin "VBUS") (pinfunction "VBUS_VBUS") (pintype "bidirectional"))
    )
    (net (code "24") (name "Net-(J$1-SIGNAL)") (class "Default")
      (node (ref "J$1") (pin "SIG") (pinfunction "SIGNAL_SIG") (pintype "bidirectional"))
      (node (ref "L4") (pin "2") (pinfunction "2_2") (pintype "passive"))
    )
    (net (code "25") (name "Net-(U$1-PadIN)") (class "Default")
      (node (ref "U$1") (pin "IN") (pinfunction "IN_IN") (pintype "bidirectional"))
      (node (ref "U$2") (pin "OUT") (pinfunction "OUT_OUT") (pintype "bidirectional"))
    )
    (net (code "26") (name "Net-(U$6-PIN2)") (class "Default")
      (node (ref "R6") (pin "2") (pinfunction "2_2") (pintype "passive"))
      (node (ref "U$6") (pin "2") (pinfunction "PIN2_2") (pintype "bidirectional"))
    )
    (net (code "27") (name "Net-(U$6-PIN4)") (class "Default")
      (node (ref "R7") (pin "1") (pinfunction "1_1") (pintype "passive"))
      (node (ref "U$6") (pin "4") (pinfunction "PIN4_4") (pintype "bidirectional"))
    )
    (net (code "28") (name "Net-(U1-PA00(XIN32{slash}SER1:0{slash}TC2:0))") (class "Default")
      (node (ref "C6") (pin "1") (pinfunction "1_1") (pintype "passive"))
      (node (ref "U1") (pin "1") (pinfunction "PA00(XIN32/SER1:0/TC2:0)_1") (pintype "bidirectional"))
      (node (ref "Y1") (pin "P$2") (pinfunction "2_P$2") (pintype "passive"))
    )
    (net (code "29") (name "Net-(U1-PA01(XOUT32{slash}SER1:1{slash}TC2:1))") (class "Default")
      (node (ref "C7") (pin "1") (pinfunction "1_1") (pintype "passive"))
      (node (ref "U1") (pin "2") (pinfunction "PA01(XOUT32/SER1:1/TC2:1)_2") (pintype "bidirectional"))
      (node (ref "Y1") (pin "P$1") (pinfunction "1_P$1") (pintype "passive"))
    )
    (net (code "30") (name "Net-(U1-VDDANA)") (class "Default")
      (node (ref "C3") (pin "1") (pinfunction "1_1") (pintype "passive"))
      (node (ref "L1") (pin "2") (pinfunction "2_2") (pintype "passive"))
      (node (ref "U1") (pin "6") (pinfunction "VDDANA_6") (pintype "bidirectional"))
    )
    (net (code "31") (name "Net-(U1-VDDCORE)") (class "Default")
      (node (ref "C4") (pin "1") (pinfunction "1_1") (pintype "passive"))
      (node (ref "U1") (pin "43") (pinfunction "VDDCORE_43") (pintype "bidirectional"))
    )
    (net (code "32") (name "Net-(U2-AVDD_PFD_CHP)") (class "Default")
      (node (ref "C23") (pin "2") (pinfunction "2_2") (pintype "passive"))
      (node (ref "U2") (pin "25") (pinfunction "AVDD_PFD_CHP_25") (pintype "bidirectional"))
    )
    (net (code "33") (name "Net-(U2-DCPL)") (class "Default")
      (node (ref "C32") (pin "2") (pinfunction "2_2") (pintype "passive"))
      (node (ref "U2") (pin "6") (pinfunction "DCPL_6") (pintype "bidirectional"))
    )
    (net (code "34") (name "Net-(U2-DCPL_PFD_CHP)") (class "Default")
      (node (ref "C24") (pin "2") (pinfunction "2_2") (pintype "passive"))
      (node (ref "U2") (pin "26") (pinfunction "DCPL_PFD_CHP_26") (pintype "bidirectional"))
    )
    (net (code "35") (name "Net-(U2-DCPL_VCO)") (class "Default")
      (node (ref "C20") (pin "1") (pinfunction "1_1") (pintype "passive"))
      (node (ref "U2") (pin "21") (pinfunction "DCPL_VCO_21") (pintype "bidirectional"))
    )
    (net (code "36") (name "Net-(U2-DCPL_XOSC)") (class "Default")
      (node (ref "C27") (pin "2") (pinfunction "2_2") (pintype "passive"))
      (node (ref "U2") (pin "29") (pinfunction "DCPL_XOSC_29") (pintype "bidirectional"))
    )
    (net (code "37") (name "Net-(U2-EXT_XOSC)") (class "Default")
      (node (ref "R14") (pin "1") (pinfunction "1_1") (pintype "passive"))
      (node (ref "U2") (pin "32") (pinfunction "EXT_XOSC_32") (pintype "bidirectional"))
    )
    (net (code "38") (name "Net-(U2-LNA_N)") (class "Default")
      (node (ref "C19") (pin "1") (pinfunction "1_1") (pintype "passive"))
      (node (ref "L7") (pin "1") (pinfunction "1_1") (pintype "passive"))
      (node (ref "L8") (pin "1") (pinfunction "1_1") (pintype "passive"))
      (node (ref "U2") (pin "20") (pinfunction "LNA_N_20") (pintype "bidirectional"))
    )
    (net (code "39") (name "Net-(U2-LNA_P)") (class "Default")
      (node (ref "C18") (pin "1") (pinfunction "1_1") (pintype "passive"))
      (node (ref "L7") (pin "2") (pinfunction "2_2") (pintype "passive"))
      (node (ref "L9") (pin "1") (pinfunction "1_1") (pintype "passive"))
      (node (ref "U2") (pin "19") (pinfunction "LNA_P_19") (pintype "bidirectional"))
    )
    (net (code "40") (name "Net-(U2-LPF0)") (class "Default")
      (node (ref "C22") (pin "2") (pinfunction "2_2") (pintype "passive"))
      (node (ref "U2") (pin "23") (pinfunction "LPF0_23") (pintype "bidirectional"))
    )
    (net (code "41") (name "Net-(U2-LPF1)") (class "Default")
      (node (ref "C22") (pin "1") (pinfunction "1_1") (pintype "passive"))
      (node (ref "U2") (pin "24") (pinfunction "LPF1_24") (pintype "bidirectional"))
    )
    (net (code "42") (name "Net-(U2-PA)") (class "Default")
      (node (ref "C13") (pin "1") (pinfunction "1_1") (pintype "passive"))
      (node (ref "L5") (pin "2") (pinfunction "2_2") (pintype "passive"))
      (node (ref "U2") (pin "17") (pinfunction "PA_17") (pintype "bidirectional"))
    )
    (net (code "43") (name "Net-(U2-RBIAS)") (class "Default")
      (node (ref "R16") (pin "1") (pinfunction "1_1") (pintype "passive"))
      (node (ref "U2") (pin "14") (pinfunction "RBIAS_14") (pintype "bidirectional"))
    )
    (net (code "44") (name "Net-(U2-TRX_SW)") (class "Default")
      (node (ref "C15") (pin "2") (pinfunction "2_2") (pintype "passive"))
      (node (ref "L6") (pin "2") (pinfunction "2_2") (pintype "passive"))
      (node (ref "U2") (pin "18") (pinfunction "TRX_SW_18") (pintype "bidirectional"))
    )
    (net (code "45") (name "Net-(U2-XOSC_Q1)") (class "Default")
      (node (ref "C29") (pin "2") (pinfunction "2_2") (pintype "passive"))
      (node (ref "U2") (pin "30") (pinfunction "XOSC_Q1_30") (pintype "bidirectional"))
      (node (ref "Y3") (pin "3") (pinfunction "2_3") (pintype "passive"))
    )
    (net (code "46") (name "Net-(U2-XOSC_Q2)") (class "Default")
      (node (ref "C28") (pin "2") (pinfunction "2_2") (pintype "passive"))
      (node (ref "U2") (pin "31") (pinfunction "XOSC_Q2_31") (pintype "bidirectional"))
      (node (ref "Y3") (pin "1") (pinfunction "1_1") (pintype "passive"))
    )
    (net (code "47") (name "Net-(U4-3D-FIX)") (class "Default")
      (node (ref "D1") (pin "A") (pinfunction "A_A") (pintype "passive"))
      (node (ref "U4") (pin "P$5") (pinfunction "3D-FIX_P$5") (pintype "bidirectional"))
    )
    (net (code "48") (name "PROG") (class "Default")
      (node (ref "R13") (pin "2") (pinfunction "2_2") (pintype "passive"))
      (node (ref "S2") (pin "1") (pinfunction "1_1") (pintype "passive"))
      (node (ref "S2") (pin "2") (pinfunction "1_2") (pintype "passive"))
      (node (ref "U1") (pin "12") (pinfunction "PA07(AIN7/SER0:3/TC1:1)_12") (pintype "bidirectional"))
    )
    (net (code "49") (name "RAW") (class "Default")
      (node (ref "J1") (pin "2") (pinfunction "+_2") (pintype "bidirectional"))
      (node (ref "R18") (pin "2") (pinfunction "2_2") (pintype "passive"))
      (node (ref "U$1") (pin "VCC") (pinfunction "VCC_VCC") (pintype "bidirectional"))
      (node (ref "U$2") (pin "VCC") (pinfunction "VCC_VCC") (pintype "bidirectional"))
      (node (ref "U$3") (pin "S1") (pinfunction "S_S1") (pintype "bidirectional"))
      (node (ref "U$3") (pin "S2") (pinfunction "S_S2") (pintype "bidirectional"))
      (node (ref "U$3") (pin "S3") (pinfunction "S_S3") (pintype "bidirectional"))
    )
    (net (code "50") (name "SENSE_A") (class "Default")
      (node (ref "R10") (pin "2") (pinfunction "2_2") (pintype "passive"))
      (node (ref "R9") (pin "1") (pinfunction "1_1") (pintype "passive"))
      (node (ref "U1") (pin "7") (pinfunction "PB08(AIN2/SER4:0/TC4:0)_7") (pintype "bidirectional"))
    )
    (net (code "51") (name "SENSE_B") (class "Default")
      (node (ref "R11") (pin "2") (pinfunction "2_2") (pintype "passive"))
      (node (ref "R12") (pin "1") (pinfunction "1_1") (pintype "passive"))
      (node (ref "U1") (pin "8") (pinfunction "PB09(AIN3/SER4:1/TC4:1)_8") (pintype "bidirectional"))
    )
    (net (code "52") (name "SENSE_BAT") (class "Default")
      (node (ref "R18") (pin "1") (pinfunction "1_1") (pintype "passive"))
      (node (ref "R19") (pin "2") (pinfunction "2_2") (pintype "passive"))
      (node (ref "U1") (pin "11") (pinfunction "PA06(AIN6/SER0:2/TC1:0)_11") (pintype "bidirectional"))
    )
    (net (code "53") (name "SPI_MISO") (class "Default")
      (node (ref "MEM") (pin "SO") (pinfunction "SO_SO") (pintype "bidirectional"))
      (node (ref "U$5") (pin "6") (pinfunction "SDO_6") (pintype "bidirectional"))
      (node (ref "U1") (pin "23") (pinfunction "PA14(XIN/SER2:2+)_23") (pintype "bidirectional"))
      (node (ref "U2") (pin "9") (pinfunction "GPOI1_9") (pintype "bidirectional"))
      (node (ref "U3") (pin "12") (pinfunction "SDO_12") (pintype "bidirectional"))
    )
    (net (code "54") (name "SPI_MOSI") (class "Default")
      (node (ref "MEM") (pin "SI") (pinfunction "SI_SI") (pintype "bidirectional"))
      (node (ref "U$5") (pin "7") (pinfunction "SDI/SDA_7") (pintype "bidirectional"))
      (node (ref "U1") (pin "22") (pinfunction "PA13(I2C/SER2:1+)_22") (pintype "bidirectional"))
      (node (ref "U2") (pin "7") (pinfunction "SI_7") (pintype "bidirectional"))
      (node (ref "U3") (pin "13") (pinfunction "SDA_13") (pintype "bidirectional"))
    )
    (net (code "55") (name "SPI_SCK") (class "Default")
      (node (ref "MEM") (pin "SCK") (pinfunction "SCK_SCK") (pintype "bidirectional"))
      (node (ref "U$5") (pin "8") (pinfunction "SCLK_8") (pintype "bidirectional"))
      (node (ref "U1") (pin "24") (pinfunction "PA15(XOUT/SER2:3+)_24") (pintype "bidirectional"))
      (node (ref "U2") (pin "8") (pinfunction "SCLK_8") (pintype "bidirectional"))
      (node (ref "U3") (pin "14") (pinfunction "SCL_14") (pintype "bidirectional"))
    )
    (net (code "56") (name "SWCLK") (class "Default")
      (node (ref "JP1") (pin "4") (pinfunction "SWDCLK/TCK_4") (pintype "bidirectional"))
      (node (ref "U1") (pin "45") (pinfunction "PA30(SWCLK/SER1:2+)_45") (pintype "bidirectional"))
    )
    (net (code "57") (name "SWDIO") (class "Default")
      (node (ref "JP1") (pin "2") (pinfunction "SWDIO/TMS_2") (pintype "bidirectional"))
      (node (ref "U1") (pin "46") (pinfunction "PA31(SWDIO/SER1:3+)_46") (pintype "bidirectional"))
    )
    (net (code "58") (name "USB_D+") (class "Default")
      (node (ref "JP4") (pin "D+") (pinfunction "D+_D+") (pintype "bidirectional"))
      (node (ref "U1") (pin "34") (pinfunction "PA25(SER3:3+)_34") (pintype "bidirectional"))
    )
    (net (code "59") (name "USB_D-") (class "Default")
      (node (ref "JP4") (pin "D-") (pinfunction "D-_D-") (pintype "bidirectional"))
      (node (ref "U1") (pin "33") (pinfunction "PA24(SER3:2+)_33") (pintype "bidirectional"))
    )
    (net (code "60") (name "unconnected-(1U2-BP-Pad4)") (class "Default")
      (node (ref "1U2") (pin "4") (pinfunction "BP_4") (pintype "input"))
    )
    (net (code "61") (name "unconnected-(J1-PAD1-PadNC1)") (class "Default")
      (node (ref "J1") (pin "NC1") (pinfunction "PAD1_NC1") (pintype "bidirectional"))
    )
    (net (code "62") (name "unconnected-(J1-PAD2-PadNC2)") (class "Default")
      (node (ref "J1") (pin "NC2") (pinfunction "PAD2_NC2") (pintype "bidirectional"))
    )
    (net (code "63") (name "unconnected-(JP1-GNDDTCT-Pad9)") (class "Default")
      (node (ref "JP1") (pin "9") (pinfunction "GNDDTCT_9") (pintype "bidirectional"))
    )
    (net (code "64") (name "unconnected-(JP1-KEY-Pad7)") (class "Default")
      (node (ref "JP1") (pin "7") (pinfunction "KEY_7") (pintype "bidirectional"))
    )
    (net (code "65") (name "unconnected-(JP1-NC{slash}TDI-Pad8)") (class "Default")
      (node (ref "JP1") (pin "8") (pinfunction "NC/TDI_8") (pintype "bidirectional"))
    )
    (net (code "66") (name "unconnected-(JP1-SWO{slash}TDO-Pad6)") (class "Default")
      (node (ref "JP1") (pin "6") (pinfunction "SWO/TDO_6") (pintype "bidirectional"))
    )
    (net (code "67") (name "unconnected-(U$1-PadCLR)") (class "Default")
      (node (ref "U$1") (pin "CLR") (pinfunction "CLR_CLR") (pintype "bidirectional"))
    )
    (net (code "68") (name "unconnected-(U$1-~{OUT}-Pad!OUT)") (class "Default")
      (node (ref "U$1") (pin "!OUT") (pinfunction "~{OUT}_!OUT") (pintype "bidirectional"))
    )
    (net (code "69") (name "unconnected-(U1-PA02(AIN0{slash}DAC)-Pad3)") (class "Default")
      (node (ref "U1") (pin "3") (pinfunction "PA02(AIN0/DAC)_3") (pintype "bidirectional"))
    )
    (net (code "70") (name "unconnected-(U1-PA03(AIN1{slash}REFA)-Pad4)") (class "Default")
      (node (ref "U1") (pin "4") (pinfunction "PA03(AIN1/REFA)_4") (pintype "bidirectional"))
    )
    (net (code "71") (name "unconnected-(U1-PA04(AIN4{slash}REFB{slash}SER0:0{slash}TC0:0)-Pad9)") (class "Default")
      (node (ref "U1") (pin "9") (pinfunction "PA04(AIN4/REFB/SER0:0/TC0:0)_9") (pintype "bidirectional"))
    )
    (net (code "72") (name "unconnected-(U1-PA05(AIN5{slash}SER0:1{slash}TC0:1)-Pad10)") (class "Default")
      (node (ref "U1") (pin "10") (pinfunction "PA05(AIN5/SER0:1/TC0:1)_10") (pintype "bidirectional"))
    )
    (net (code "73") (name "unconnected-(U1-PA11(AIN19{slash}SER0:3+)-Pad16)") (class "Default")
      (node (ref "U1") (pin "16") (pinfunction "PA11(AIN19/SER0:3+)_16") (pintype "bidirectional"))
    )
    (net (code "74") (name "unconnected-(U1-PA17(I2C{slash}SER1:1+)-Pad26)") (class "Default")
      (node (ref "U1") (pin "26") (pinfunction "PA17(I2C/SER1:1+)_26") (pintype "bidirectional"))
    )
    (net (code "75") (name "unconnected-(U1-PA18(SER1:2+)-Pad27)") (class "Default")
      (node (ref "U1") (pin "27") (pinfunction "PA18(SER1:2+)_27") (pintype "bidirectional"))
    )
    (net (code "76") (name "unconnected-(U1-PA19(SER1:3+)-Pad28)") (class "Default")
      (node (ref "U1") (pin "28") (pinfunction "PA19(SER1:3+)_28") (pintype "bidirectional"))
    )
    (net (code "77") (name "unconnected-(U1-PA20(SER5:2+)-Pad29)") (class "Default")
      (node (ref "U1") (pin "29") (pinfunction "PA20(SER5:2+)_29") (pintype "bidirectional"))
    )
    (net (code "78") (name "unconnected-(U1-PA21(SER5:3+)-Pad30)") (class "Default")
      (node (ref "U1") (pin "30") (pinfunction "PA21(SER5:3+)_30") (pintype "bidirectional"))
    )
    (net (code "79") (name "unconnected-(U1-PA22(I2C{slash}SER3:0+)-Pad31)") (class "Default")
      (node (ref "U1") (pin "31") (pinfunction "PA22(I2C/SER3:0+)_31") (pintype "bidirectional"))
    )
    (net (code "80") (name "unconnected-(U1-PA23(I2C{slash}SER3:0+)-Pad32)") (class "Default")
      (node (ref "U1") (pin "32") (pinfunction "PA23(I2C/SER3:0+)_32") (pintype "bidirectional"))
    )
    (net (code "81") (name "unconnected-(U1-PA27-Pad39)") (class "Default")
      (node (ref "U1") (pin "39") (pinfunction "PA27_39") (pintype "bidirectional"))
    )
    (net (code "82") (name "unconnected-(U1-PA28-Pad41)") (class "Default")
      (node (ref "U1") (pin "41") (pinfunction "PA28_41") (pintype "bidirectional"))
    )
    (net (code "83") (name "unconnected-(U1-PB10(SER4:2+)-Pad19)") (class "Default")
      (node (ref "U1") (pin "19") (pinfunction "PB10(SER4:2+)_19") (pintype "bidirectional"))
    )
    (net (code "84") (name "unconnected-(U1-PB11(SER4:3+)-Pad20)") (class "Default")
      (node (ref "U1") (pin "20") (pinfunction "PB11(SER4:3+)_20") (pintype "bidirectional"))
    )
    (net (code "85") (name "unconnected-(U2-GPIO0-Pad10)") (class "Default")
      (node (ref "U2") (pin "10") (pinfunction "GPIO0_10") (pintype "bidirectional"))
    )
    (net (code "86") (name "unconnected-(U2-GPIO2-Pad4)") (class "Default")
      (node (ref "U2") (pin "4") (pinfunction "GPIO2_4") (pintype "bidirectional"))
    )
    (net (code "87") (name "unconnected-(U2-GPIO3-Pad3)") (class "Default")
      (node (ref "U2") (pin "3") (pinfunction "GPIO3_3") (pintype "bidirectional"))
    )
    (net (code "88") (name "unconnected-(U2-N.C.-Pad16)") (class "Default")
      (node (ref "U2") (pin "16") (pinfunction "N.C._16") (pintype "bidirectional"))
    )
    (net (code "89") (name "unconnected-(U2-RESET_N-Pad2)") (class "Default")
      (node (ref "U2") (pin "2") (pinfunction "RESET_N_2") (pintype "bidirectional"))
    )
    (net (code "90") (name "unconnected-(U3-INT1-Pad8)") (class "Default")
      (node (ref "U3") (pin "8") (pinfunction "INT1_8") (pintype "bidirectional"))
    )
    (net (code "91") (name "unconnected-(U3-INT2-Pad9)") (class "Default")
      (node (ref "U3") (pin "9") (pinfunction "INT2_9") (pintype "bidirectional"))
    )
    (net (code "92") (name "unconnected-(U3-NC-Pad3)") (class "Default")
      (node (ref "U3") (pin "3") (pinfunction "NC_3") (pintype "bidirectional"))
    )
    (net (code "93") (name "unconnected-(U3-NC-Pad10)") (class "Default")
      (node (ref "U3") (pin "10") (pinfunction "NC_10") (pintype "bidirectional"))
    )
    (net (code "94") (name "unconnected-(U3-NC-Pad11)") (class "Default")
      (node (ref "U3") (pin "11") (pinfunction "NC_11") (pintype "bidirectional"))
    )
    (net (code "95") (name "unconnected-(U4-1PPS-PadP$13)") (class "Default")
      (node (ref "U4") (pin "P$13") (pinfunction "1PPS_P$13") (pintype "bidirectional"))
    )
    (net (code "96") (name "unconnected-(U4-EX_ANT-PadP$11)") (class "Default")
      (node (ref "U4") (pin "P$11") (pinfunction "EX_ANT_P$11") (pintype "bidirectional"))
    )
    (net (code "97") (name "unconnected-(U4-NC-PadP$6)") (class "Default")
      (node (ref "U4") (pin "P$6") (pinfunction "NC_P$6") (pintype "bidirectional"))
    )
    (net (code "98") (name "unconnected-(U4-NC-PadP$7)") (class "Default")
      (node (ref "U4") (pin "P$7") (pinfunction "NC_P$7") (pintype "bidirectional"))
    )
    (net (code "99") (name "unconnected-(U4-NC-PadP$15)") (class "Default")
      (node (ref "U4") (pin "P$15") (pinfunction "NC_P$15") (pintype "bidirectional"))
    )
    (net (code "100") (name "unconnected-(U4-NC-PadP$16)") (class "Default")
      (node (ref "U4") (pin "P$16") (pinfunction "NC_P$16") (pintype "bidirectional"))
    )
    (net (code "101") (name "unconnected-(U4-NC-PadP$17)") (class "Default")
      (node (ref "U4") (pin "P$17") (pinfunction "NC_P$17") (pintype "bidirectional"))
    )
    (net (code "102") (name "unconnected-(U4-NC-PadP$18)") (class "Default")
      (node (ref "U4") (pin "P$18") (pinfunction "NC_P$18") (pintype "bidirectional"))
    )
    (net (code "103") (name "unconnected-(U4-NC-PadP$20)") (class "Default")
      (node (ref "U4") (pin "P$20") (pinfunction "NC_P$20") (pintype "bidirectional"))
    )
    (net (code "104") (name "unconnected-(U4-NRESET-PadP$2)") (class "Default")
      (node (ref "U4") (pin "P$2") (pinfunction "NRESET_P$2") (pintype "bidirectional"))
    )
    (net (code "105") (name "unconnected-(U4-RTCM-PadP$14)") (class "Default")
      (node (ref "U4") (pin "P$14") (pinfunction "RTCM_P$14") (pintype "bidirectional"))
    )
    (net (code "106") (name "unconnected-(U4-VBACKUP-PadP$4)") (class "Default")
      (node (ref "U4") (pin "P$4") (pinfunction "VBACKUP_P$4") (pintype "bidirectional"))
    )
  )
)
